# v1_0.net
KiCad netlist of a schematic drawn in Altium Designer
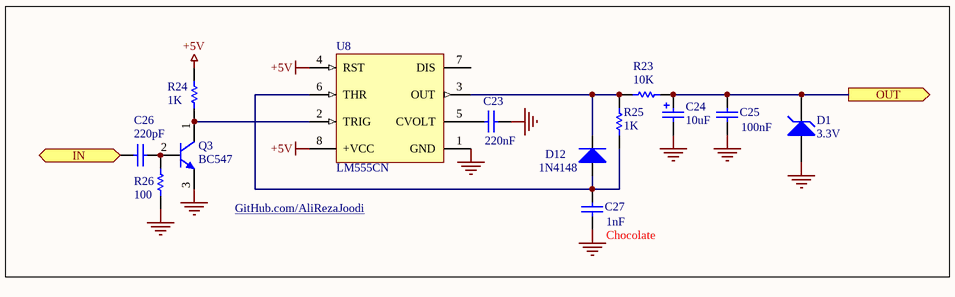
[diagram p0: v1.0.SchDoc]

(export (version "E")
  (design (tool "Eeschema 10.0.6"))
  (components
    (comp (ref "C23")
      (value "220nF")
      (footprint "CAPNTO5.08-7.37x3.94")
      (description "Capacitor")
      (fields (field (name "Comment") "Cap") (field (name "PUBLISHER") "Altium Limited"))
      (libsource (lib "") (part "Cap_1"))
    )
    (comp (ref "C24")
      (value "10uF")
      (footprint "CAPPR2.5-5x6")
      (description "Polarized Capacitor (Radial)")
      (fields
        (field (name "MANUFACTURER") "Generic Components")
        (field (name "Comment") "Cap Pol1")
        (field (name "PUBLISHER") "Altium Limited")
      )
      (libsource (lib "Miscellaneous Devices") (part "Cap Pol1"))
    )
    (comp (ref "C25")
      (value "100nF")
      (footprint "CAPNTO2.54-3.05x1.78A")
      (description "Capacitor")
      (fields (field (name "Comment") "Cap") (field (name "PUBLISHER") "Altium Limited"))
      (libsource (lib "Miscellaneous Devices") (part "Cap"))
    )
    (comp (ref "C26")
      (value "220pF")
      (footprint "CAPNTO2.54-3.56x2.03")
      (description "Capacitor")
      (fields (field (name "Comment") "Cap") (field (name "PUBLISHER") "Altium Limited"))
      (libsource (lib "") (part "Cap_1"))
    )
    (comp (ref "C27")
      (value "1nF")
      (footprint "CAPNTO2.54-3.56x2.03")
      (description "Capacitor")
      (fields (field (name "Comment") "Cap") (field (name "PUBLISHER") "Altium Limited"))
      (libsource (lib "Miscellaneous Devices") (part "Cap"))
    )
    (comp (ref "D1")
      (value "3.3V")
      (footprint "DIODE0.4_Glass")
      (description "Zener Diode")
      (fields (field (name "MANUFACTURER") "Generic Components") (field (name "PUBLISHER") "Altium Limited"))
      (libsource (lib "Miscellaneous Devices") (part "D Zener"))
    )
    (comp (ref "D12")
      (value "1N4148")
      (footprint "DIODE0.4_Glass")
      (description "Default Diode")
      (fields
        (field (name "MANUFACTURER") "Generic Components")
        (field (name "Comment") "Diode")
        (field (name "PUBLISHER") "Altium Limited")
      )
      (libsource (lib "Miscellaneous Devices") (part "Diode"))
    )
    (comp (ref "Q3")
      (value "BC547")
      (footprint "TO92C")
      (description "NPN Bipolar Transistor")
      (fields
        (field (name "MANUFACTURER") "Generic Components")
        (field (name "Comment") "Q3")
        (field (name "PUBLISHER") "Altium Limited")
      )
      (libsource (lib "Miscellaneous Devices") (part "NPN"))
    )
    (comp (ref "R23")
      (value "10K")
      (footprint "AXIAL-0.4")
      (description "Resistor")
      (fields (field (name "Comment") "Res1") (field (name "PUBLISHER") "Altium Limited"))
      (libsource (lib "Miscellaneous Devices") (part "Res1"))
    )
    (comp (ref "R24")
      (value "1K")
      (footprint "AXIAL-0.4")
      (description "Resistor")
      (fields (field (name "Comment") "Res1") (field (name "PUBLISHER") "Altium Limited"))
      (libsource (lib "Miscellaneous Devices") (part "Res1"))
    )
    (comp (ref "R25")
      (value "1K")
      (footprint "AXIAL-0.4")
      (description "Resistor")
      (fields (field (name "Comment") "Res1") (field (name "PUBLISHER") "Altium Limited"))
      (libsource (lib "Miscellaneous Devices") (part "Res1"))
    )
    (comp (ref "R26")
      (value "100")
      (footprint "AXIAL-0.4")
      (description "Resistor")
      (fields (field (name "Comment") "Res1") (field (name "PUBLISHER") "Altium Limited"))
      (libsource (lib "Miscellaneous Devices") (part "Res1"))
    )
    (comp (ref "U8")
      (value "LM555CN")
      (footprint "DIP-8")
      (description "Timer")
      (fields
        (field (name "MANUFACTURER") "National Semiconductor")
        (field (name "DIGIKEYPARTNUMBER") "LM555CNNS-ND")
        (field (name "PUBLISHER") "Altium Limited")
      )
      (libsource (lib "NSC Analog") (part "LM555CN"))
    )
  )
  (nets
    (net (code "1") (name "+5V") (class "Default")
      (node (ref "R24") (pin "1") (pinfunction "1_1") (pintype "passive"))
      (node (ref "U8") (pin "4") (pinfunction "RST_4") (pintype "input"))
      (node (ref "U8") (pin "8") (pinfunction "+VCC_8") (pintype "power_in"))
    )
    (net (code "2") (name "/IN") (class "Default")
      (node (ref "C26") (pin "2") (pinfunction "2_2") (pintype "passive"))
    )
    (net (code "3") (name "/OUT") (class "Default")
      (node (ref "C24") (pin "1") (pinfunction "1_1") (pintype "passive"))
      (node (ref "C25") (pin "1") (pinfunction "1_1") (pintype "passive"))
      (node (ref "D1") (pin "2") (pinfunction "K_2") (pintype "passive"))
      (node (ref "R23") (pin "2") (pinfunction "2_2") (pintype "passive"))
    )
    (net (code "4") (name "GND") (class "Default")
      (node (ref "C23") (pin "1") (pinfunction "1_1") (pintype "passive"))
      (node (ref "C24") (pin "2") (pinfunction "2_2") (pintype "passive"))
      (node (ref "C25") (pin "2") (pinfunction "2_2") (pintype "passive"))
      (node (ref "C27") (pin "2") (pinfunction "2_2") (pintype "passive"))
      (node (ref "D1") (pin "1") (pinfunction "A_1") (pintype "passive"))
      (node (ref "Q3") (pin "3") (pinfunction "E_3") (pintype "passive"))
      (node (ref "R26") (pin "2") (pinfunction "2_2") (pintype "passive"))
      (node (ref "U8") (pin "1") (pinfunction "GND_1") (pintype "power_in"))
    )
    (net (code "5") (name "Net-(D12-A)") (class "Default")
      (node (ref "C27") (pin "1") (pinfunction "1_1") (pintype "passive"))
      (node (ref "D12") (pin "1") (pinfunction "A_1") (pintype "passive"))
      (node (ref "R25") (pin "1") (pinfunction "1_1") (pintype "passive"))
      (node (ref "U8") (pin "6") (pinfunction "THR_6") (pintype "input"))
    )
    (net (code "6") (name "Net-(D12-K)") (class "Default")
      (node (ref "D12") (pin "2") (pinfunction "K_2") (pintype "passive"))
      (node (ref "R23") (pin "1") (pinfunction "1_1") (pintype "passive"))
      (node (ref "R25") (pin "2") (pinfunction "2_2") (pintype "passive"))
      (node (ref "U8") (pin "3") (pinfunction "OUT_3") (pintype "output"))
    )
    (net (code "7") (name "Net-(Q3-B)") (class "Default")
      (node (ref "C26") (pin "1") (pinfunction "1_1") (pintype "passive"))
      (node (ref "Q3") (pin "2") (pinfunction "B_2") (pintype "passive"))
      (node (ref "R26") (pin "1") (pinfunction "1_1") (pintype "passive"))
    )
    (net (code "8") (name "Net-(Q3-C)") (class "Default")
      (node (ref "Q3") (pin "1") (pinfunction "C_1") (pintype "passive"))
      (node (ref "R24") (pin "2") (pinfunction "2_2") (pintype "passive"))
      (node (ref "U8") (pin "2") (pinfunction "TRIG_2") (pintype "input"))
    )
    (net (code "9") (name "Net-(U8-CVOLT)") (class "Default")
      (node (ref "C23") (pin "2") (pinfunction "2_2") (pintype "passive"))
      (node (ref "U8") (pin "5") (pinfunction "CVOLT_5") (pintype "passive"))
    )
    (net (code "10") (name "unconnected-(U8-DIS-Pad7)") (class "Default")
      (node (ref "U8") (pin "7") (pinfunction "DIS_7") (pintype "open_collector"))
    )
  )
)
